# Schematico-amplificatore-audio.net
KiCad netlist of a schematic drawn in EAGLE
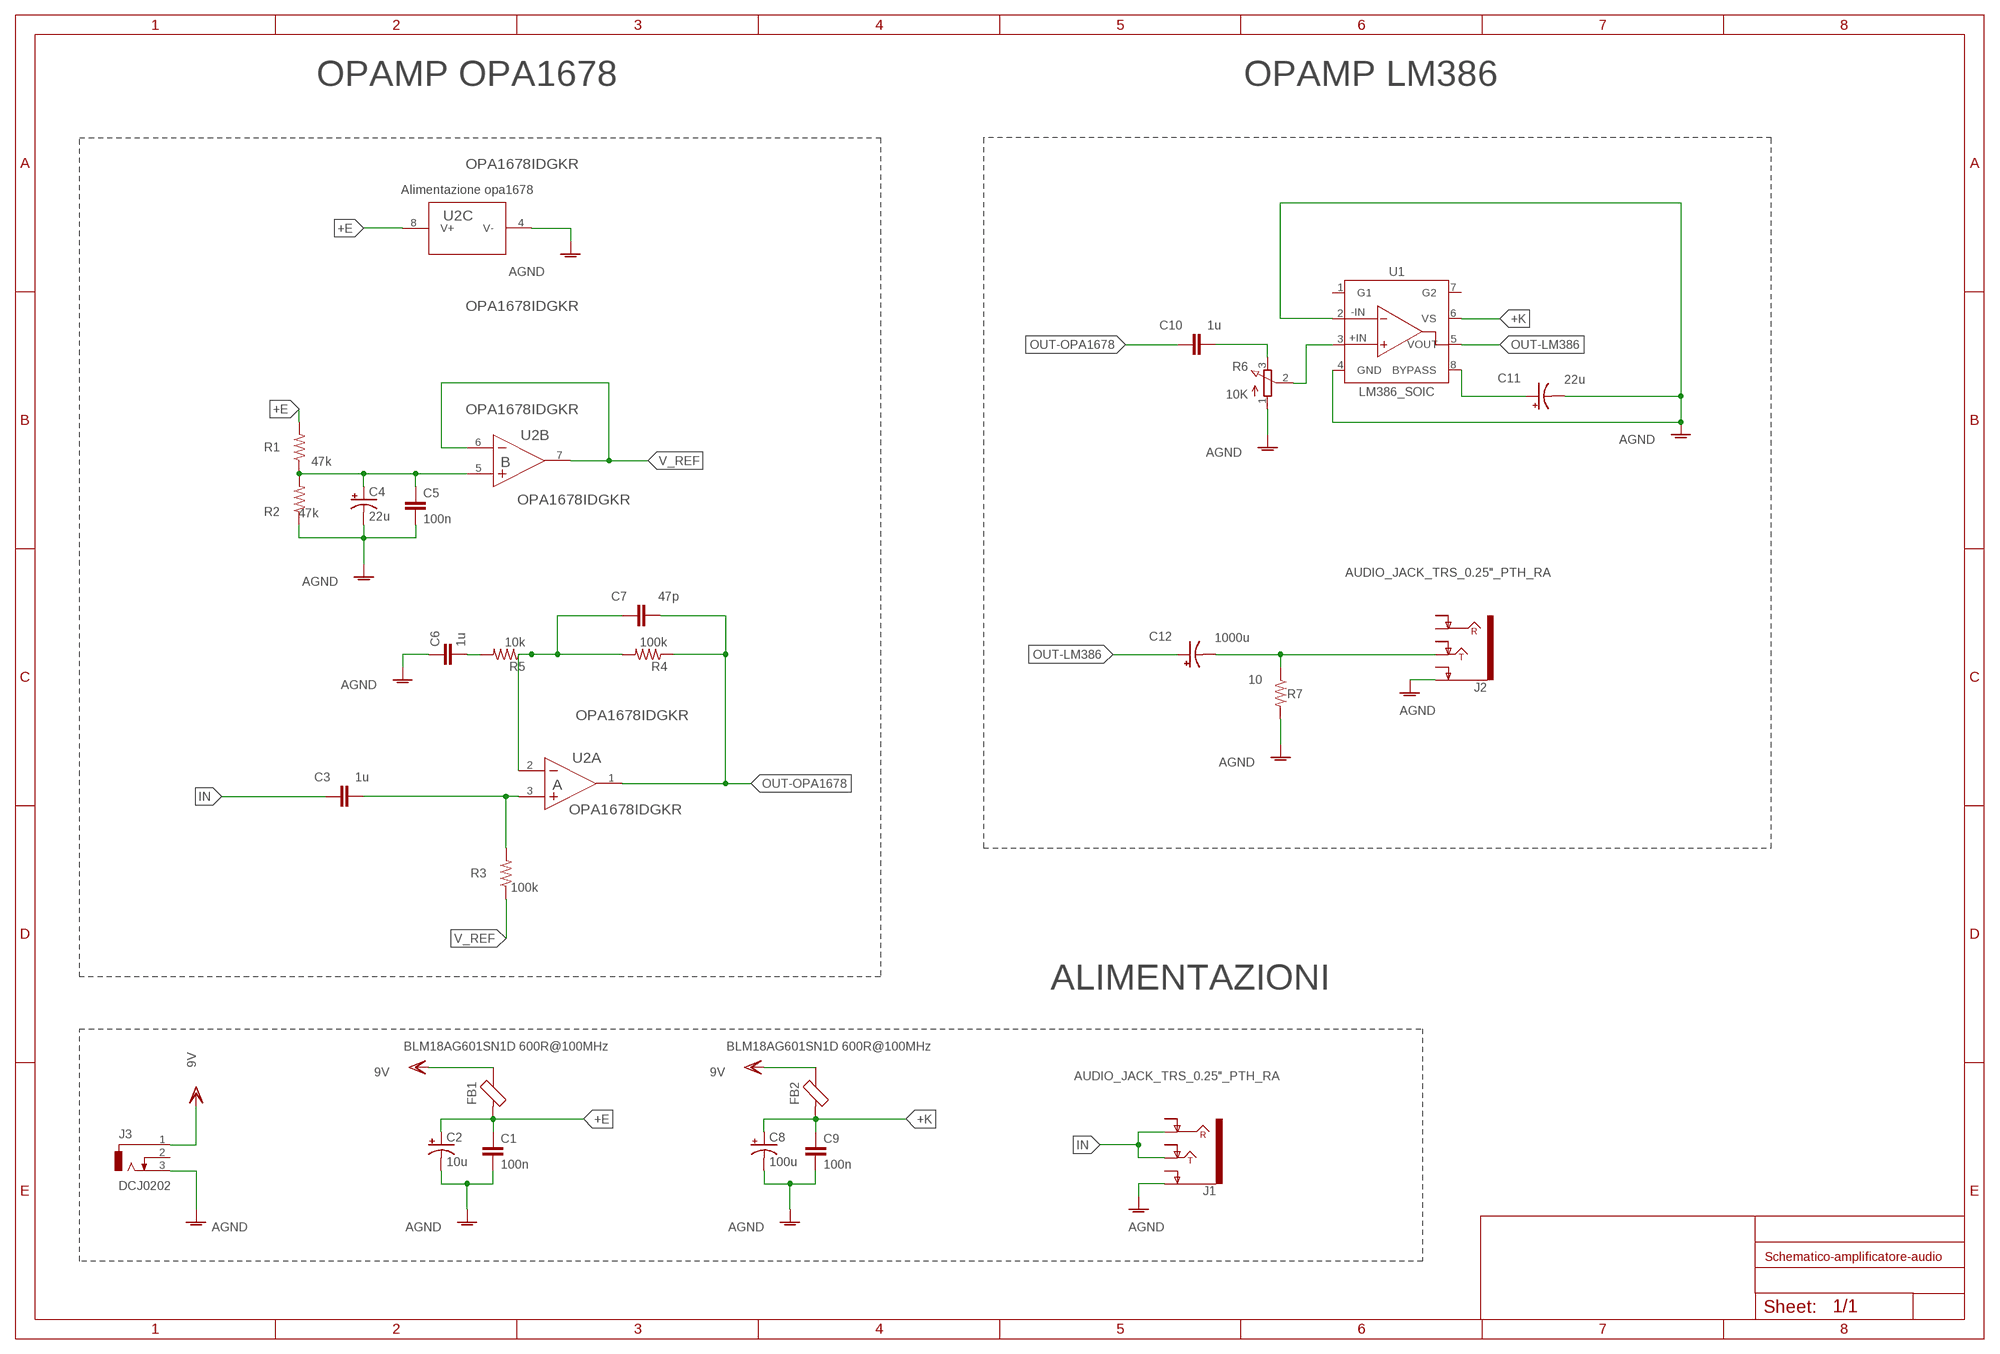
[diagram p0: schematic, sheet 1]

(export (version "E")
  (design (tool "Eeschema 10.0.6"))
  (components
    (comp (ref "C1")
      (value "100n")
      (footprint "eagle-import:C0603")
      (libsource (lib "eagle-import") (part "C-EUC0603"))
    )
    (comp (ref "C2")
      (value "10u")
      (footprint "eagle-import:CT3216")
      (libsource (lib "eagle-import") (part "CPOL-USCT3216"))
    )
    (comp (ref "C3")
      (value "1u")
      (footprint "eagle-import:C0603")
      (libsource (lib "eagle-import") (part "C-EUC0603"))
    )
    (comp (ref "C4")
      (value "22u")
      (footprint "eagle-import:CT3216")
      (libsource (lib "eagle-import") (part "CPOL-USCT3216"))
    )
    (comp (ref "C5")
      (value "100n")
      (footprint "eagle-import:C0603")
      (libsource (lib "eagle-import") (part "C-EUC0603"))
    )
    (comp (ref "C6")
      (value "1u")
      (footprint "eagle-import:C0603")
      (libsource (lib "eagle-import") (part "C-EUC0603"))
    )
    (comp (ref "C7")
      (value "47p")
      (footprint "eagle-import:C0603")
      (libsource (lib "eagle-import") (part "C-EUC0603"))
    )
    (comp (ref "C8")
      (value "100u")
      (footprint "eagle-import:CT3216")
      (libsource (lib "eagle-import") (part "CPOL-USCT3216"))
    )
    (comp (ref "C9")
      (value "100n")
      (footprint "eagle-import:C0603")
      (libsource (lib "eagle-import") (part "C-EUC0603"))
    )
    (comp (ref "C10")
      (value "1u")
      (footprint "eagle-import:C0603")
      (libsource (lib "eagle-import") (part "C-EUC0603"))
    )
    (comp (ref "C11")
      (value "22u")
      (footprint "eagle-import:CT3216")
      (libsource (lib "eagle-import") (part "CPOL-USCT3216"))
    )
    (comp (ref "C12")
      (value "1000u")
      (footprint "eagle-import:CT3216")
      (libsource (lib "eagle-import") (part "CPOL-USCT3216"))
    )
    (comp (ref "FB1")
      (value "BLM18AG601SN1D 600R@100MHz")
      (footprint "eagle-import:BEADC1608X95N")
      (fields (field (name "MANUFACTURER") "Murata Electronics") (field (name "MPN") "BLM18AG601SN1D"))
      (libsource (lib "eagle-import") (part "FB__0603(1608)BLM18AG601SN1D"))
    )
    (comp (ref "FB2")
      (value "BLM18AG601SN1D 600R@100MHz")
      (footprint "eagle-import:BEADC1608X95N")
      (fields (field (name "MANUFACTURER") "Murata Electronics") (field (name "MPN") "BLM18AG601SN1D"))
      (libsource (lib "eagle-import") (part "FB__0603(1608)BLM18AG601SN1D"))
    )
    (comp (ref "J1")
      (value "AUDIO_JACK_TRS_0.25\"_PTH_RA")
      (footprint "eagle-import:AUDIO_JACK_0.25__TRS_PTH_RA")
      (libsource (lib "eagle-import") (part "AUDIO_JACK_TRS_0.25{dblquote}_PTH_RA"))
    )
    (comp (ref "J2")
      (value "AUDIO_JACK_TRS_0.25\"_PTH_RA")
      (footprint "eagle-import:AUDIO_JACK_0.25__TRS_PTH_RA")
      (libsource (lib "eagle-import") (part "AUDIO_JACK_TRS_0.25{dblquote}_PTH_RA"))
    )
    (comp (ref "J3")
      (value "DCJ0202")
      (footprint "eagle-import:DCJ0202")
      (libsource (lib "eagle-import") (part "DCJ0202"))
    )
    (comp (ref "R1")
      (value "47k")
      (footprint "eagle-import:R0603")
      (libsource (lib "eagle-import") (part "R-US_R0603"))
    )
    (comp (ref "R2")
      (value "47k")
      (footprint "eagle-import:R0603")
      (libsource (lib "eagle-import") (part "R-US_R0603"))
    )
    (comp (ref "R3")
      (value "100k")
      (footprint "eagle-import:R0603")
      (libsource (lib "eagle-import") (part "R-US_R0603"))
    )
    (comp (ref "R4")
      (value "100k")
      (footprint "eagle-import:R0603")
      (libsource (lib "eagle-import") (part "R-US_R0603"))
    )
    (comp (ref "R5")
      (value "10k")
      (footprint "eagle-import:R0603")
      (libsource (lib "eagle-import") (part "R-US_R0603"))
    )
    (comp (ref "R6")
      (value "10K")
      (footprint "eagle-import:3RP_1610N")
      (libsource (lib "eagle-import") (part "3RP/1610N"))
    )
    (comp (ref "R7")
      (value "10")
      (footprint "eagle-import:R0603")
      (libsource (lib "eagle-import") (part "R-US_R0603"))
    )
    (comp (ref "U1")
      (value "LM386_SOIC")
      (footprint "eagle-import:SOIC127P600X175-8N")
      (libsource (lib "eagle-import") (part "LM386_SOIC"))
    )
    (comp (ref "U2")
      (value "OPA1678IDGKR")
      (footprint "eagle-import:DGK0008A_N")
      (fields (field (name "COPYRIGHT") "Copyright (C) 2026 Ultra Librarian. All rights reserved."))
      (libsource (lib "eagle-import") (part "OPA1678IDGKR"))
    )
  )
  (nets
    (net (code "1") (name "+E") (class "Default")
      (node (ref "C1") (pin "1") (pinfunction "1_1") (pintype "passive"))
      (node (ref "C2") (pin "+") (pinfunction "+_+") (pintype "passive"))
      (node (ref "FB1") (pin "1") (pinfunction "1_1") (pintype "passive"))
      (node (ref "R1") (pin "2") (pinfunction "2_2") (pintype "passive"))
      (node (ref "U2") (pin "8") (pinfunction "V+_8") (pintype "power_in"))
    )
    (net (code "2") (name "+K") (class "Default")
      (node (ref "C8") (pin "+") (pinfunction "+_+") (pintype "passive"))
      (node (ref "C9") (pin "1") (pinfunction "1_1") (pintype "passive"))
      (node (ref "FB2") (pin "1") (pinfunction "1_1") (pintype "passive"))
      (node (ref "U1") (pin "6") (pinfunction "VS_6") (pintype "bidirectional"))
    )
    (net (code "3") (name "9V") (class "Default")
      (node (ref "FB1") (pin "2") (pinfunction "2_2") (pintype "passive"))
      (node (ref "FB2") (pin "2") (pinfunction "2_2") (pintype "passive"))
      (node (ref "J3") (pin "1") (pinfunction "1_1") (pintype "passive"))
    )
    (net (code "4") (name "AGND") (class "Default")
      (node (ref "C1") (pin "2") (pinfunction "2_2") (pintype "passive"))
      (node (ref "C11") (pin "-") (pinfunction "-_-") (pintype "passive"))
      (node (ref "C2") (pin "-") (pinfunction "-_-") (pintype "passive"))
      (node (ref "C4") (pin "-") (pinfunction "-_-") (pintype "passive"))
      (node (ref "C5") (pin "2") (pinfunction "2_2") (pintype "passive"))
      (node (ref "C6") (pin "1") (pinfunction "1_1") (pintype "passive"))
      (node (ref "C8") (pin "-") (pinfunction "-_-") (pintype "passive"))
      (node (ref "C9") (pin "2") (pinfunction "2_2") (pintype "passive"))
      (node (ref "J1") (pin "SLEEVE") (pinfunction "EARTH_SLEEVE") (pintype "bidirectional"))
      (node (ref "J2") (pin "SLEEVE") (pinfunction "EARTH_SLEEVE") (pintype "bidirectional"))
      (node (ref "J3") (pin "3") (pinfunction "3_3") (pintype "passive"))
      (node (ref "R2") (pin "1") (pinfunction "1_1") (pintype "passive"))
      (node (ref "R6") (pin "1") (pinfunction "A_1") (pintype "passive"))
      (node (ref "R7") (pin "2") (pinfunction "2_2") (pintype "passive"))
      (node (ref "U1") (pin "2") (pinfunction "-IN_2") (pintype "input"))
      (node (ref "U1") (pin "4") (pinfunction "GND_4") (pintype "bidirectional"))
      (node (ref "U2") (pin "4") (pinfunction "V-_4") (pintype "power_in"))
    )
    (net (code "5") (name "IN") (class "Default")
      (node (ref "C3") (pin "1") (pinfunction "1_1") (pintype "passive"))
      (node (ref "J1") (pin "RING") (pinfunction "RING_RING") (pintype "bidirectional"))
      (node (ref "J1") (pin "TIP") (pinfunction "TIP_TIP") (pintype "bidirectional"))
    )
    (net (code "6") (name "Net-(C6-Pad2)") (class "Default")
      (node (ref "C6") (pin "2") (pinfunction "2_2") (pintype "passive"))
      (node (ref "R5") (pin "2") (pinfunction "2_2") (pintype "passive"))
    )
    (net (code "7") (name "Net-(C12-Pad-)") (class "Default")
      (node (ref "C12") (pin "-") (pinfunction "-_-") (pintype "passive"))
      (node (ref "J2") (pin "TIP") (pinfunction "TIP_TIP") (pintype "bidirectional"))
      (node (ref "R7") (pin "1") (pinfunction "1_1") (pintype "passive"))
    )
    (net (code "8") (name "Net-(R6-E)") (class "Default")
      (node (ref "C10") (pin "2") (pinfunction "2_2") (pintype "passive"))
      (node (ref "R6") (pin "3") (pinfunction "E_3") (pintype "passive"))
    )
    (net (code "9") (name "Net-(R6-S)") (class "Default")
      (node (ref "R6") (pin "2") (pinfunction "S_2") (pintype "passive"))
      (node (ref "U1") (pin "3") (pinfunction "+IN_3") (pintype "input"))
    )
    (net (code "10") (name "Net-(U1-BYPASS)") (class "Default")
      (node (ref "C11") (pin "+") (pinfunction "+_+") (pintype "passive"))
      (node (ref "U1") (pin "8") (pinfunction "BYPASS_8") (pintype "passive"))
    )
    (net (code "11") (name "Net-(U2A-IN+)") (class "Default")
      (node (ref "C3") (pin "2") (pinfunction "2_2") (pintype "passive"))
      (node (ref "R3") (pin "2") (pinfunction "2_2") (pintype "passive"))
      (node (ref "U2") (pin "3") (pinfunction "IN+_3") (pintype "input"))
    )
    (net (code "12") (name "Net-(U2A-IN-)") (class "Default")
      (node (ref "C7") (pin "1") (pinfunction "1_1") (pintype "passive"))
      (node (ref "R4") (pin "2") (pinfunction "2_2") (pintype "passive"))
      (node (ref "R5") (pin "1") (pinfunction "1_1") (pintype "passive"))
      (node (ref "U2") (pin "2") (pinfunction "IN-_2") (pintype "input"))
    )
    (net (code "13") (name "Net-(U2B-IN+)") (class "Default")
      (node (ref "C4") (pin "+") (pinfunction "+_+") (pintype "passive"))
      (node (ref "C5") (pin "1") (pinfunction "1_1") (pintype "passive"))
      (node (ref "R1") (pin "1") (pinfunction "1_1") (pintype "passive"))
      (node (ref "R2") (pin "2") (pinfunction "2_2") (pintype "passive"))
      (node (ref "U2") (pin "5") (pinfunction "IN+_5") (pintype "input"))
    )
    (net (code "14") (name "OUT-LM386") (class "Default")
      (node (ref "C12") (pin "+") (pinfunction "+_+") (pintype "passive"))
      (node (ref "U1") (pin "5") (pinfunction "VOUT_5") (pintype "output"))
    )
    (net (code "15") (name "OUT-OPA1678") (class "Default")
      (node (ref "C10") (pin "1") (pinfunction "1_1") (pintype "passive"))
      (node (ref "C7") (pin "2") (pinfunction "2_2") (pintype "passive"))
      (node (ref "R4") (pin "1") (pinfunction "1_1") (pintype "passive"))
      (node (ref "U2") (pin "1") (pinfunction "OUT_1") (pintype "output"))
    )
    (net (code "16") (name "V_REF") (class "Default")
      (node (ref "R3") (pin "1") (pinfunction "1_1") (pintype "passive"))
      (node (ref "U2") (pin "6") (pinfunction "IN-_6") (pintype "input"))
      (node (ref "U2") (pin "7") (pinfunction "OUT_7") (pintype "output"))
    )
    (net (code "17") (name "unconnected-(J1-EARTH-NORM-PadSLEEVE-NORM)") (class "Default")
      (node (ref "J1") (pin "SLEEVE-NORM") (pinfunction "EARTH-NORM_SLEEVE-NORM") (pintype "bidirectional"))
    )
    (net (code "18") (name "unconnected-(J1-PadRING-NORM)") (class "Default")
      (node (ref "J1") (pin "RING-NORM") (pinfunction "RING-NORM_RING-NORM") (pintype "bidirectional"))
    )
    (net (code "19") (name "unconnected-(J1-PadTIP-NORM)") (class "Default")
      (node (ref "J1") (pin "TIP-NORM") (pinfunction "TIP-NORM_TIP-NORM") (pintype "bidirectional"))
    )
    (net (code "20") (name "unconnected-(J2-EARTH-NORM-PadSLEEVE-NORM)") (class "Default")
      (node (ref "J2") (pin "SLEEVE-NORM") (pinfunction "EARTH-NORM_SLEEVE-NORM") (pintype "bidirectional"))
    )
    (net (code "21") (name "unconnected-(J2-PadRING)") (class "Default")
      (node (ref "J2") (pin "RING") (pinfunction "RING_RING") (pintype "bidirectional"))
    )
    (net (code "22") (name "unconnected-(J2-PadRING-NORM)") (class "Default")
      (node (ref "J2") (pin "RING-NORM") (pinfunction "RING-NORM_RING-NORM") (pintype "bidirectional"))
    )
    (net (code "23") (name "unconnected-(J2-PadTIP-NORM)") (class "Default")
      (node (ref "J2") (pin "TIP-NORM") (pinfunction "TIP-NORM_TIP-NORM") (pintype "bidirectional"))
    )
    (net (code "24") (name "unconnected-(J3-Pad2)") (class "Default")
      (node (ref "J3") (pin "2") (pinfunction "2_2") (pintype "passive"))
    )
    (net (code "25") (name "unconnected-(U1-G1-Pad1)") (class "Default")
      (node (ref "U1") (pin "1") (pinfunction "G1_1") (pintype "passive"))
    )
    (net (code "26") (name "unconnected-(U1-G2-Pad7)") (class "Default")
      (node (ref "U1") (pin "7") (pinfunction "G2_7") (pintype "passive"))
    )
  )
)
